# sensor_current.net
KiCad netlist of a schematic drawn in EAGLE
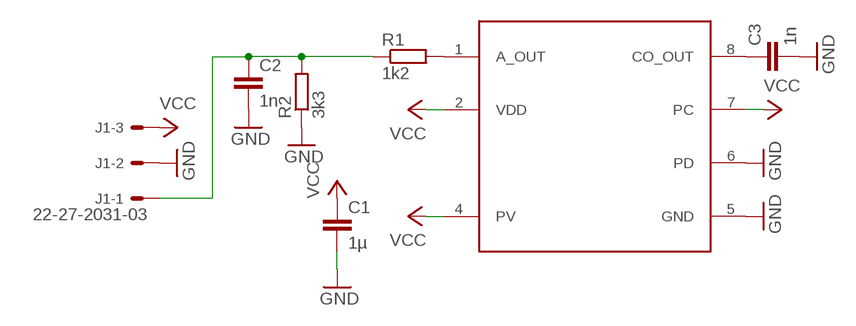
[diagram p0: schematic, sheet 1]

(export (version "E")
  (design (tool "Eeschema 10.0.6"))
  (components
    (comp (ref "C1")
      (value "1µ")
      (footprint "eagle-import:C025-024X044")
      (libsource (lib "eagle-import") (part "C-EU025-024X044"))
    )
    (comp (ref "C2")
      (value "1n")
      (footprint "eagle-import:C025-024X044")
      (libsource (lib "eagle-import") (part "C-EU025-024X044"))
    )
    (comp (ref "C3")
      (value "1n")
      (footprint "eagle-import:C025-024X044")
      (libsource (lib "eagle-import") (part "C-EU025-024X044"))
    )
    (comp (ref "IC1")
      (value "MLX91205")
      (footprint "eagle-import:SO-08")
      (libsource (lib "eagle-import") (part "MLX91205"))
    )
    (comp (ref "J1")
      (value "22-27-2031-03")
      (footprint "eagle-import:6410-03")
      (libsource (lib "eagle-import") (part "22-?-0327-2031"))
    )
    (comp (ref "R1")
      (value "1k2")
      (footprint "eagle-import:0204V")
      (libsource (lib "eagle-import") (part "R-EU_0204/2V"))
    )
    (comp (ref "R2")
      (value "3k3")
      (footprint "eagle-import:0204V")
      (libsource (lib "eagle-import") (part "R-EU_0204/2V"))
    )
  )
  (nets
    (net (code "1") (name "GND") (class "Default")
      (node (ref "C1") (pin "2") (pinfunction "2_2") (pintype "passive"))
      (node (ref "C2") (pin "2") (pinfunction "2_2") (pintype "passive"))
      (node (ref "C3") (pin "2") (pinfunction "2_2") (pintype "passive"))
      (node (ref "IC1") (pin "5") (pinfunction "GND_5") (pintype "bidirectional"))
      (node (ref "IC1") (pin "6") (pinfunction "PD_6") (pintype "bidirectional"))
      (node (ref "J1") (pin "2") (pinfunction "S_2") (pintype "passive"))
      (node (ref "R2") (pin "1") (pinfunction "1_1") (pintype "passive"))
    )
    (net (code "2") (name "Net-(IC1-A_OUT)") (class "Default")
      (node (ref "IC1") (pin "1") (pinfunction "A_OUT_1") (pintype "bidirectional"))
      (node (ref "R1") (pin "2") (pinfunction "2_2") (pintype "passive"))
    )
    (net (code "3") (name "Net-(IC1-CO_OUT)") (class "Default")
      (node (ref "C3") (pin "1") (pinfunction "1_1") (pintype "passive"))
      (node (ref "IC1") (pin "8") (pinfunction "CO_OUT_8") (pintype "bidirectional"))
    )
    (net (code "4") (name "Net-(J1A-S)") (class "Default")
      (node (ref "C2") (pin "1") (pinfunction "1_1") (pintype "passive"))
      (node (ref "J1") (pin "1") (pinfunction "S_1") (pintype "passive"))
      (node (ref "R1") (pin "1") (pinfunction "1_1") (pintype "passive"))
      (node (ref "R2") (pin "2") (pinfunction "2_2") (pintype "passive"))
    )
    (net (code "5") (name "VCC") (class "Default")
      (node (ref "C1") (pin "1") (pinfunction "1_1") (pintype "passive"))
      (node (ref "IC1") (pin "2") (pinfunction "VDD_2") (pintype "bidirectional"))
      (node (ref "IC1") (pin "4") (pinfunction "PV_4") (pintype "bidirectional"))
      (node (ref "IC1") (pin "7") (pinfunction "PC_7") (pintype "bidirectional"))
      (node (ref "J1") (pin "3") (pinfunction "S_3") (pintype "passive"))
    )
  )
)
